# PIC_16F877A_Board_V3.net
KiCad netlist of a schematic drawn in EAGLE
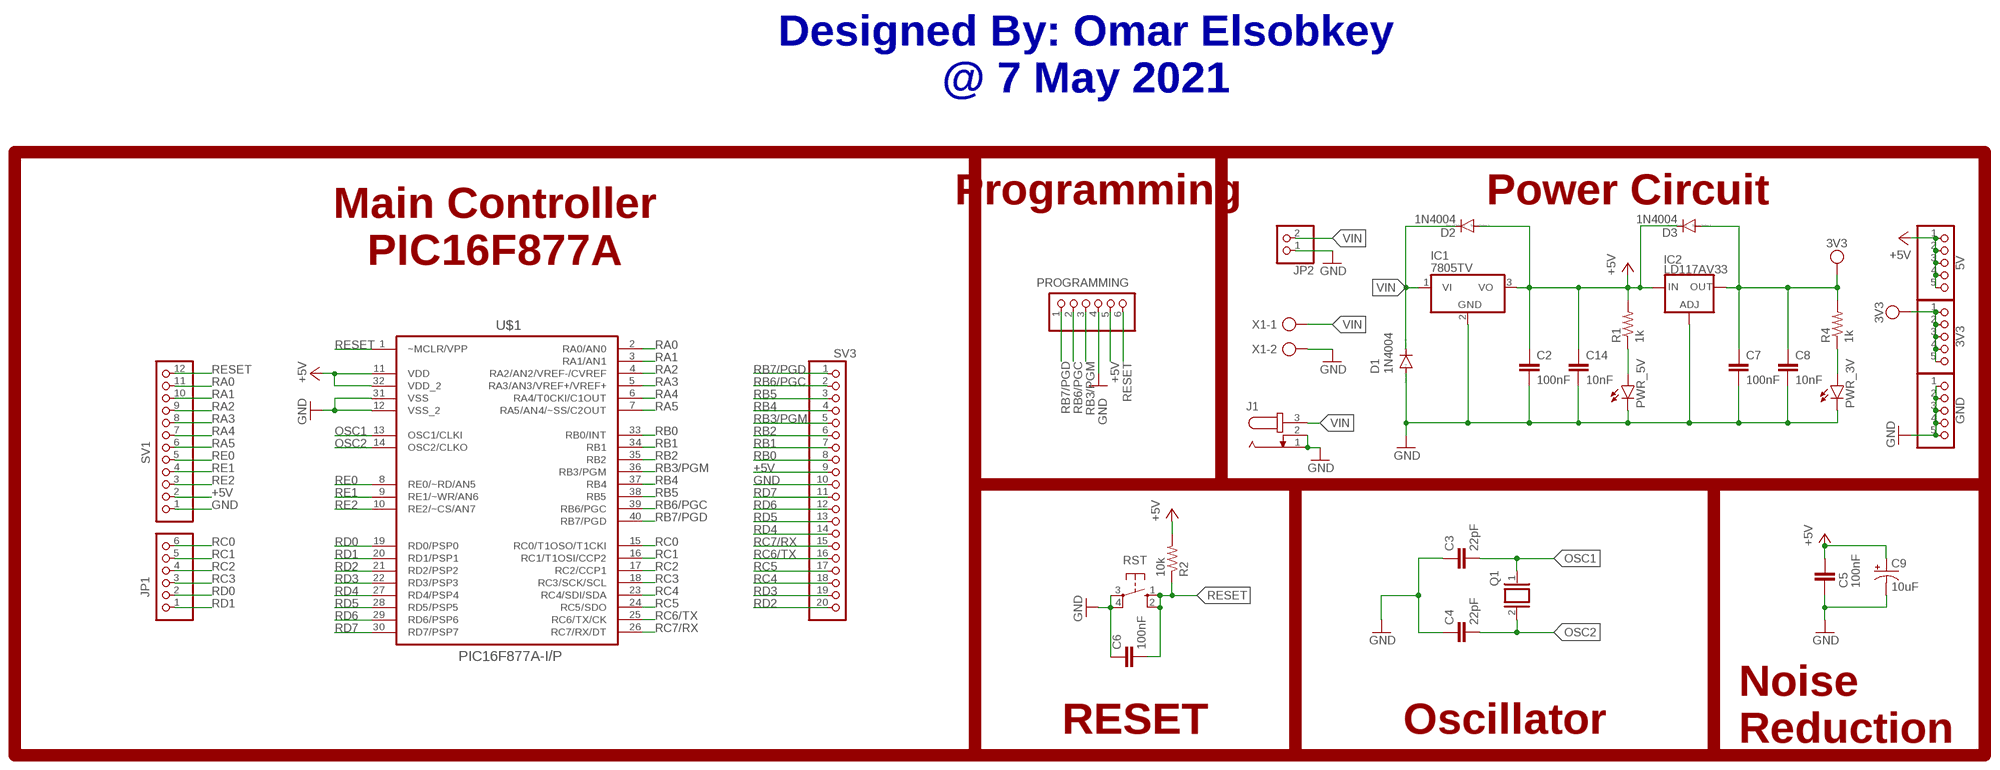
[diagram p0: schematic, sheet 1]

(export (version "E")
  (design (tool "Eeschema 10.0.6"))
  (components
    (comp (ref "3V3")
      (value "PINHD-1X5")
      (footprint "eagle-import:1X05")
      (libsource (lib "eagle-import") (part "PINHD-1X5"))
    )
    (comp (ref "5V")
      (value "PINHD-1X5")
      (footprint "eagle-import:1X05")
      (libsource (lib "eagle-import") (part "PINHD-1X5"))
    )
    (comp (ref "C2")
      (value "100nF")
      (footprint "eagle-import:C025-025X050")
      (libsource (lib "eagle-import") (part "C-EU025-025X050"))
    )
    (comp (ref "C3")
      (value "22pF")
      (footprint "eagle-import:C025-025X050")
      (libsource (lib "eagle-import") (part "C-EU025-025X050"))
    )
    (comp (ref "C4")
      (value "22pF")
      (footprint "eagle-import:C025-025X050")
      (libsource (lib "eagle-import") (part "C-EU025-025X050"))
    )
    (comp (ref "C5")
      (value "100nF")
      (footprint "eagle-import:C025-025X050")
      (libsource (lib "eagle-import") (part "C-EU025-025X050"))
    )
    (comp (ref "C6")
      (value "100nF")
      (footprint "eagle-import:C025-025X050")
      (libsource (lib "eagle-import") (part "C-EU025-025X050"))
    )
    (comp (ref "C7")
      (value "100nF")
      (footprint "eagle-import:C025-025X050")
      (libsource (lib "eagle-import") (part "C-EU025-025X050"))
    )
    (comp (ref "C8")
      (value "10nF")
      (footprint "eagle-import:C025-025X050")
      (libsource (lib "eagle-import") (part "C-EU025-025X050"))
    )
    (comp (ref "C9")
      (value "10uF")
      (footprint "eagle-import:CPOL-RADIAL-2.5MM-5MM-KIT")
      (libsource (lib "eagle-import") (part "10UF-POLAR-RADIAL-2.5MM-KIT-25V-20%"))
    )
    (comp (ref "C14")
      (value "10nF")
      (footprint "eagle-import:C025-025X050")
      (libsource (lib "eagle-import") (part "C-EU025-025X050"))
    )
    (comp (ref "D1")
      (value "1N4004")
      (footprint "eagle-import:DO41-10")
      (libsource (lib "eagle-import") (part "1N4004"))
    )
    (comp (ref "D2")
      (value "1N4004")
      (footprint "eagle-import:DO41-10")
      (libsource (lib "eagle-import") (part "1N4004"))
    )
    (comp (ref "D3")
      (value "1N4004")
      (footprint "eagle-import:DO41-10")
      (libsource (lib "eagle-import") (part "1N4004"))
    )
    (comp (ref "GND")
      (value "PINHD-1X5")
      (footprint "eagle-import:1X05")
      (libsource (lib "eagle-import") (part "PINHD-1X5"))
    )
    (comp (ref "IC1")
      (value "7805TV")
      (footprint "eagle-import:TO220V")
      (libsource (lib "eagle-import") (part "78TV05"))
    )
    (comp (ref "IC2")
      (value "LD117AV33")
      (footprint "eagle-import:TO220L1")
      (libsource (lib "eagle-import") (part "LD117A?V33"))
    )
    (comp (ref "J1")
      (value "JACK-PLUG0")
      (footprint "eagle-import:SPC4077")
      (libsource (lib "eagle-import") (part "JACK-PLUG0"))
    )
    (comp (ref "JP1")
      (value "PINHD-1X6")
      (footprint "eagle-import:1X06")
      (libsource (lib "eagle-import") (part "PINHD-1X6"))
    )
    (comp (ref "JP2")
      (value "PINHD-1X2")
      (footprint "eagle-import:1X02")
      (libsource (lib "eagle-import") (part "PINHD-1X2"))
    )
    (comp (ref "PROGRAMMING")
      (value "PINHD-1X6")
      (footprint "eagle-import:1X06")
      (libsource (lib "eagle-import") (part "PINHD-1X6"))
    )
    (comp (ref "PWR_3V")
      (value "LED3MM")
      (footprint "eagle-import:LED3MM")
      (libsource (lib "eagle-import") (part "LED3MM"))
    )
    (comp (ref "PWR_5V")
      (value "LED3MM")
      (footprint "eagle-import:LED3MM")
      (libsource (lib "eagle-import") (part "LED3MM"))
    )
    (comp (ref "Q1")
      (value "XTAL/S")
      (footprint "eagle-import:QS")
      (libsource (lib "eagle-import") (part "XTAL/S"))
    )
    (comp (ref "R1")
      (value "1k")
      (footprint "eagle-import:AXIAL-0.3")
      (libsource (lib "eagle-import") (part "RESISTORAXIAL-0.3"))
    )
    (comp (ref "R2")
      (value "10k")
      (footprint "eagle-import:AXIAL-0.3")
      (libsource (lib "eagle-import") (part "RESISTORAXIAL-0.3"))
    )
    (comp (ref "R4")
      (value "1k")
      (footprint "eagle-import:AXIAL-0.3")
      (libsource (lib "eagle-import") (part "RESISTORAXIAL-0.3"))
    )
    (comp (ref "RST")
      (value "10-XX")
      (footprint "eagle-import:B3F-10XX")
      (fields (field (name "MPN") "B3F-1000"))
      (libsource (lib "eagle-import") (part "10-XX"))
    )
    (comp (ref "SV1")
      (value "PINHD-1X12")
      (footprint "eagle-import:1X12")
      (libsource (lib "eagle-import") (part "PINHD-1X12"))
    )
    (comp (ref "SV3")
      (value "PINHD-1X20")
      (footprint "eagle-import:1X20")
      (libsource (lib "eagle-import") (part "PINHD-1X20"))
    )
    (comp (ref "U$1")
      (value "PIC16F877A-I/P")
      (footprint "eagle-import:16F877A")
      (fields (field (name "MF") "Microchip"))
      (libsource (lib "eagle-import") (part "PIC16F877A-I/P"))
    )
    (comp (ref "X1")
      (value "AK500/2-H")
      (footprint "eagle-import:AK500_2-H")
      (libsource (lib "eagle-import") (part "AK500/2-H"))
    )
  )
  (nets
    (net (code "1") (name "+5V") (class "Default")
      (node (ref "5V") (pin "1") (pinfunction "1_1") (pintype "passive"))
      (node (ref "5V") (pin "2") (pinfunction "2_2") (pintype "passive"))
      (node (ref "5V") (pin "3") (pinfunction "3_3") (pintype "passive"))
      (node (ref "5V") (pin "4") (pinfunction "4_4") (pintype "passive"))
      (node (ref "5V") (pin "5") (pinfunction "5_5") (pintype "passive"))
      (node (ref "C14") (pin "1") (pinfunction "1_1") (pintype "passive"))
      (node (ref "C2") (pin "1") (pinfunction "1_1") (pintype "passive"))
      (node (ref "C5") (pin "2") (pinfunction "2_2") (pintype "passive"))
      (node (ref "C9") (pin "1") (pinfunction "+_1") (pintype "passive"))
      (node (ref "D2") (pin "A") (pinfunction "A_A") (pintype "passive"))
      (node (ref "D3") (pin "C") (pinfunction "C_C") (pintype "passive"))
      (node (ref "IC1") (pin "3") (pinfunction "VO_3") (pintype "passive"))
      (node (ref "IC2") (pin "3") (pinfunction "IN_3") (pintype "input"))
      (node (ref "PROGRAMMING") (pin "5") (pinfunction "5_5") (pintype "passive"))
      (node (ref "R1") (pin "P$2") (pinfunction "2_P$2") (pintype "passive"))
      (node (ref "R2") (pin "P$2") (pinfunction "2_P$2") (pintype "passive"))
      (node (ref "SV1") (pin "2") (pinfunction "2_2") (pintype "passive"))
      (node (ref "SV3") (pin "9") (pinfunction "9_9") (pintype "passive"))
      (node (ref "U$1") (pin "11") (pinfunction "VDD_11") (pintype "power_in"))
      (node (ref "U$1") (pin "32") (pinfunction "VDD_2_32") (pintype "power_in"))
    )
    (net (code "2") (name "/RA0") (class "Default")
      (node (ref "SV1") (pin "11") (pinfunction "11_11") (pintype "passive"))
      (node (ref "U$1") (pin "2") (pinfunction "RA0/AN0_2") (pintype "bidirectional"))
    )
    (net (code "3") (name "/RA1") (class "Default")
      (node (ref "SV1") (pin "10") (pinfunction "10_10") (pintype "passive"))
      (node (ref "U$1") (pin "3") (pinfunction "RA1/AN1_3") (pintype "bidirectional"))
    )
    (net (code "4") (name "/RA2") (class "Default")
      (node (ref "SV1") (pin "9") (pinfunction "9_9") (pintype "passive"))
      (node (ref "U$1") (pin "4") (pinfunction "RA2/AN2/VREF-/CVREF_4") (pintype "bidirectional"))
    )
    (net (code "5") (name "/RA3") (class "Default")
      (node (ref "SV1") (pin "8") (pinfunction "8_8") (pintype "passive"))
      (node (ref "U$1") (pin "5") (pinfunction "RA3/AN3/VREF+/VREF+_5") (pintype "bidirectional"))
    )
    (net (code "6") (name "/RA4") (class "Default")
      (node (ref "SV1") (pin "7") (pinfunction "7_7") (pintype "passive"))
      (node (ref "U$1") (pin "6") (pinfunction "RA4/T0CKI/C1OUT_6") (pintype "bidirectional"))
    )
    (net (code "7") (name "/RA5") (class "Default")
      (node (ref "SV1") (pin "6") (pinfunction "6_6") (pintype "passive"))
      (node (ref "U$1") (pin "7") (pinfunction "RA5/AN4/~{SS/C2OUT}_7") (pintype "bidirectional"))
    )
    (net (code "8") (name "/RB0") (class "Default")
      (node (ref "SV3") (pin "8") (pinfunction "8_8") (pintype "passive"))
      (node (ref "U$1") (pin "33") (pinfunction "RB0/INT_33") (pintype "bidirectional"))
    )
    (net (code "9") (name "/RB1") (class "Default")
      (node (ref "SV3") (pin "7") (pinfunction "7_7") (pintype "passive"))
      (node (ref "U$1") (pin "34") (pinfunction "RB1_34") (pintype "bidirectional"))
    )
    (net (code "10") (name "/RB2") (class "Default")
      (node (ref "SV3") (pin "6") (pinfunction "6_6") (pintype "passive"))
      (node (ref "U$1") (pin "35") (pinfunction "RB2_35") (pintype "bidirectional"))
    )
    (net (code "11") (name "/RB3{slash}PGM") (class "Default")
      (node (ref "PROGRAMMING") (pin "3") (pinfunction "3_3") (pintype "passive"))
      (node (ref "SV3") (pin "5") (pinfunction "5_5") (pintype "passive"))
      (node (ref "U$1") (pin "36") (pinfunction "RB3/PGM_36") (pintype "bidirectional"))
    )
    (net (code "12") (name "/RB4") (class "Default")
      (node (ref "SV3") (pin "4") (pinfunction "4_4") (pintype "passive"))
      (node (ref "U$1") (pin "37") (pinfunction "RB4_37") (pintype "bidirectional"))
    )
    (net (code "13") (name "/RB5") (class "Default")
      (node (ref "SV3") (pin "3") (pinfunction "3_3") (pintype "passive"))
      (node (ref "U$1") (pin "38") (pinfunction "RB5_38") (pintype "bidirectional"))
    )
    (net (code "14") (name "/RB6{slash}PGC") (class "Default")
      (node (ref "PROGRAMMING") (pin "2") (pinfunction "2_2") (pintype "passive"))
      (node (ref "SV3") (pin "2") (pinfunction "2_2") (pintype "passive"))
      (node (ref "U$1") (pin "39") (pinfunction "RB6/PGC_39") (pintype "bidirectional"))
    )
    (net (code "15") (name "/RB7{slash}PGD") (class "Default")
      (node (ref "PROGRAMMING") (pin "1") (pinfunction "1_1") (pintype "passive"))
      (node (ref "SV3") (pin "1") (pinfunction "1_1") (pintype "passive"))
      (node (ref "U$1") (pin "40") (pinfunction "RB7/PGD_40") (pintype "bidirectional"))
    )
    (net (code "16") (name "/RC0") (class "Default")
      (node (ref "JP1") (pin "6") (pinfunction "6_6") (pintype "passive"))
      (node (ref "U$1") (pin "15") (pinfunction "RC0/T1OSO/T1CKI_15") (pintype "bidirectional"))
    )
    (net (code "17") (name "/RC1") (class "Default")
      (node (ref "JP1") (pin "5") (pinfunction "5_5") (pintype "passive"))
      (node (ref "U$1") (pin "16") (pinfunction "RC1/T1OSI/CCP2_16") (pintype "bidirectional"))
    )
    (net (code "18") (name "/RC2") (class "Default")
      (node (ref "JP1") (pin "4") (pinfunction "4_4") (pintype "passive"))
      (node (ref "U$1") (pin "17") (pinfunction "RC2/CCP1_17") (pintype "bidirectional"))
    )
    (net (code "19") (name "/RC3") (class "Default")
      (node (ref "JP1") (pin "3") (pinfunction "3_3") (pintype "passive"))
      (node (ref "U$1") (pin "18") (pinfunction "RC3/SCK/SCL_18") (pintype "bidirectional"))
    )
    (net (code "20") (name "/RC4") (class "Default")
      (node (ref "SV3") (pin "18") (pinfunction "18_18") (pintype "passive"))
      (node (ref "U$1") (pin "23") (pinfunction "RC4/SDI/SDA_23") (pintype "bidirectional"))
    )
    (net (code "21") (name "/RC5") (class "Default")
      (node (ref "SV3") (pin "17") (pinfunction "17_17") (pintype "passive"))
      (node (ref "U$1") (pin "24") (pinfunction "RC5/SDO_24") (pintype "bidirectional"))
    )
    (net (code "22") (name "/RC6{slash}TX") (class "Default")
      (node (ref "SV3") (pin "16") (pinfunction "16_16") (pintype "passive"))
      (node (ref "U$1") (pin "25") (pinfunction "RC6/TX/CK_25") (pintype "bidirectional"))
    )
    (net (code "23") (name "/RC7{slash}RX") (class "Default")
      (node (ref "SV3") (pin "15") (pinfunction "15_15") (pintype "passive"))
      (node (ref "U$1") (pin "26") (pinfunction "RC7/RX/DT_26") (pintype "bidirectional"))
    )
    (net (code "24") (name "/RD0") (class "Default")
      (node (ref "JP1") (pin "2") (pinfunction "2_2") (pintype "passive"))
      (node (ref "U$1") (pin "19") (pinfunction "RD0/PSP0_19") (pintype "bidirectional"))
    )
    (net (code "25") (name "/RD1") (class "Default")
      (node (ref "JP1") (pin "1") (pinfunction "1_1") (pintype "passive"))
      (node (ref "U$1") (pin "20") (pinfunction "RD1/PSP1_20") (pintype "bidirectional"))
    )
    (net (code "26") (name "/RD2") (class "Default")
      (node (ref "SV3") (pin "20") (pinfunction "20_20") (pintype "passive"))
      (node (ref "U$1") (pin "21") (pinfunction "RD2/PSP2_21") (pintype "bidirectional"))
    )
    (net (code "27") (name "/RD3") (class "Default")
      (node (ref "SV3") (pin "19") (pinfunction "19_19") (pintype "passive"))
      (node (ref "U$1") (pin "22") (pinfunction "RD3/PSP3_22") (pintype "bidirectional"))
    )
    (net (code "28") (name "/RD4") (class "Default")
      (node (ref "SV3") (pin "14") (pinfunction "14_14") (pintype "passive"))
      (node (ref "U$1") (pin "27") (pinfunction "RD4/PSP4_27") (pintype "bidirectional"))
    )
    (net (code "29") (name "/RD5") (class "Default")
      (node (ref "SV3") (pin "13") (pinfunction "13_13") (pintype "passive"))
      (node (ref "U$1") (pin "28") (pinfunction "RD5/PSP5_28") (pintype "bidirectional"))
    )
    (net (code "30") (name "/RD6") (class "Default")
      (node (ref "SV3") (pin "12") (pinfunction "12_12") (pintype "passive"))
      (node (ref "U$1") (pin "29") (pinfunction "RD6/PSP6_29") (pintype "bidirectional"))
    )
    (net (code "31") (name "/RD7") (class "Default")
      (node (ref "SV3") (pin "11") (pinfunction "11_11") (pintype "passive"))
      (node (ref "U$1") (pin "30") (pinfunction "RD7/PSP7_30") (pintype "bidirectional"))
    )
    (net (code "32") (name "/RE0") (class "Default")
      (node (ref "SV1") (pin "5") (pinfunction "5_5") (pintype "passive"))
      (node (ref "U$1") (pin "8") (pinfunction "RE0/~{RD/AN5}_8") (pintype "bidirectional"))
    )
    (net (code "33") (name "/RE1") (class "Default")
      (node (ref "SV1") (pin "4") (pinfunction "4_4") (pintype "passive"))
      (node (ref "U$1") (pin "9") (pinfunction "RE1/~{WR/AN6}_9") (pintype "bidirectional"))
    )
    (net (code "34") (name "/RE2") (class "Default")
      (node (ref "SV1") (pin "3") (pinfunction "3_3") (pintype "passive"))
      (node (ref "U$1") (pin "10") (pinfunction "RE2/~{CS/AN7}_10") (pintype "bidirectional"))
    )
    (net (code "35") (name "3V3") (class "Default")
      (node (ref "3V3") (pin "1") (pinfunction "1_1") (pintype "passive"))
      (node (ref "3V3") (pin "2") (pinfunction "2_2") (pintype "passive"))
      (node (ref "3V3") (pin "3") (pinfunction "3_3") (pintype "passive"))
      (node (ref "3V3") (pin "4") (pinfunction "4_4") (pintype "passive"))
      (node (ref "3V3") (pin "5") (pinfunction "5_5") (pintype "passive"))
      (node (ref "C7") (pin "1") (pinfunction "1_1") (pintype "passive"))
      (node (ref "C8") (pin "1") (pinfunction "1_1") (pintype "passive"))
      (node (ref "D3") (pin "A") (pinfunction "A_A") (pintype "passive"))
      (node (ref "IC2") (pin "2") (pinfunction "OUT_2") (pintype "passive"))
      (node (ref "R4") (pin "P$2") (pinfunction "2_P$2") (pintype "passive"))
    )
    (net (code "36") (name "GND") (class "Default")
      (node (ref "C14") (pin "2") (pinfunction "2_2") (pintype "passive"))
      (node (ref "C2") (pin "2") (pinfunction "2_2") (pintype "passive"))
      (node (ref "C3") (pin "1") (pinfunction "1_1") (pintype "passive"))
      (node (ref "C4") (pin "1") (pinfunction "1_1") (pintype "passive"))
      (node (ref "C5") (pin "1") (pinfunction "1_1") (pintype "passive"))
      (node (ref "C6") (pin "1") (pinfunction "1_1") (pintype "passive"))
      (node (ref "C7") (pin "2") (pinfunction "2_2") (pintype "passive"))
      (node (ref "C8") (pin "2") (pinfunction "2_2") (pintype "passive"))
      (node (ref "C9") (pin "2") (pinfunction "-_2") (pintype "passive"))
      (node (ref "D1") (pin "A") (pinfunction "A_A") (pintype "passive"))
      (node (ref "GND") (pin "1") (pinfunction "1_1") (pintype "passive"))
      (node (ref "GND") (pin "2") (pinfunction "2_2") (pintype "passive"))
      (node (ref "GND") (pin "3") (pinfunction "3_3") (pintype "passive"))
      (node (ref "GND") (pin "4") (pinfunction "4_4") (pintype "passive"))
      (node (ref "GND") (pin "5") (pinfunction "5_5") (pintype "passive"))
      (node (ref "IC1") (pin "2") (pinfunction "GND_2") (pintype "passive"))
      (node (ref "IC2") (pin "1") (pinfunction "ADJ_1") (pintype "input"))
      (node (ref "J1") (pin "1") (pinfunction "1_1") (pintype "passive"))
      (node (ref "J1") (pin "2") (pinfunction "2_2") (pintype "passive"))
      (node (ref "JP2") (pin "1") (pinfunction "1_1") (pintype "passive"))
      (node (ref "PROGRAMMING") (pin "4") (pinfunction "4_4") (pintype "passive"))
      (node (ref "PWR_3V") (pin "K") (pinfunction "C_K") (pintype "passive"))
      (node (ref "PWR_5V") (pin "K") (pinfunction "C_K") (pintype "passive"))
      (node (ref "RST") (pin "3") (pinfunction "P_3") (pintype "passive"))
      (node (ref "RST") (pin "4") (pinfunction "P1_4") (pintype "passive"))
      (node (ref "SV1") (pin "1") (pinfunction "1_1") (pintype "passive"))
      (node (ref "SV3") (pin "10") (pinfunction "10_10") (pintype "passive"))
      (node (ref "U$1") (pin "12") (pinfunction "VSS_2_12") (pintype "power_in"))
      (node (ref "U$1") (pin "31") (pinfunction "VSS_31") (pintype "power_in"))
      (node (ref "X1") (pin "2") (pinfunction "KL_2") (pintype "passive"))
    )
    (net (code "37") (name "Net-(R1-1)") (class "Default")
      (node (ref "PWR_5V") (pin "A") (pinfunction "A_A") (pintype "passive"))
      (node (ref "R1") (pin "P$1") (pinfunction "1_P$1") (pintype "passive"))
    )
    (net (code "38") (name "Net-(R4-1)") (class "Default")
      (node (ref "PWR_3V") (pin "A") (pinfunction "A_A") (pintype "passive"))
      (node (ref "R4") (pin "P$1") (pinfunction "1_P$1") (pintype "passive"))
    )
    (net (code "39") (name "OSC1") (class "Default")
      (node (ref "C3") (pin "2") (pinfunction "2_2") (pintype "passive"))
      (node (ref "Q1") (pin "1") (pinfunction "1_1") (pintype "passive"))
      (node (ref "U$1") (pin "13") (pinfunction "OSC1/CLKI_13") (pintype "input"))
    )
    (net (code "40") (name "OSC2") (class "Default")
      (node (ref "C4") (pin "2") (pinfunction "2_2") (pintype "passive"))
      (node (ref "Q1") (pin "2") (pinfunction "2_2") (pintype "passive"))
      (node (ref "U$1") (pin "14") (pinfunction "OSC2/CLKO_14") (pintype "output"))
    )
    (net (code "41") (name "RESET") (class "Default")
      (node (ref "C6") (pin "2") (pinfunction "2_2") (pintype "passive"))
      (node (ref "PROGRAMMING") (pin "6") (pinfunction "6_6") (pintype "passive"))
      (node (ref "R2") (pin "P$1") (pinfunction "1_P$1") (pintype "passive"))
      (node (ref "RST") (pin "1") (pinfunction "S_1") (pintype "passive"))
      (node (ref "RST") (pin "2") (pinfunction "S1_2") (pintype "passive"))
      (node (ref "SV1") (pin "12") (pinfunction "12_12") (pintype "passive"))
      (node (ref "U$1") (pin "1") (pinfunction "~{MCLR/VPP}_1") (pintype "input"))
    )
    (net (code "42") (name "VIN") (class "Default")
      (node (ref "D1") (pin "C") (pinfunction "C_C") (pintype "passive"))
      (node (ref "D2") (pin "C") (pinfunction "C_C") (pintype "passive"))
      (node (ref "IC1") (pin "1") (pinfunction "VI_1") (pintype "input"))
      (node (ref "J1") (pin "3") (pinfunction "3_3") (pintype "passive"))
      (node (ref "JP2") (pin "2") (pinfunction "2_2") (pintype "passive"))
      (node (ref "X1") (pin "1") (pinfunction "KL_1") (pintype "passive"))
    )
  )
)
